# MCU.net
KiCad netlist of a schematic drawn in Altium Designer
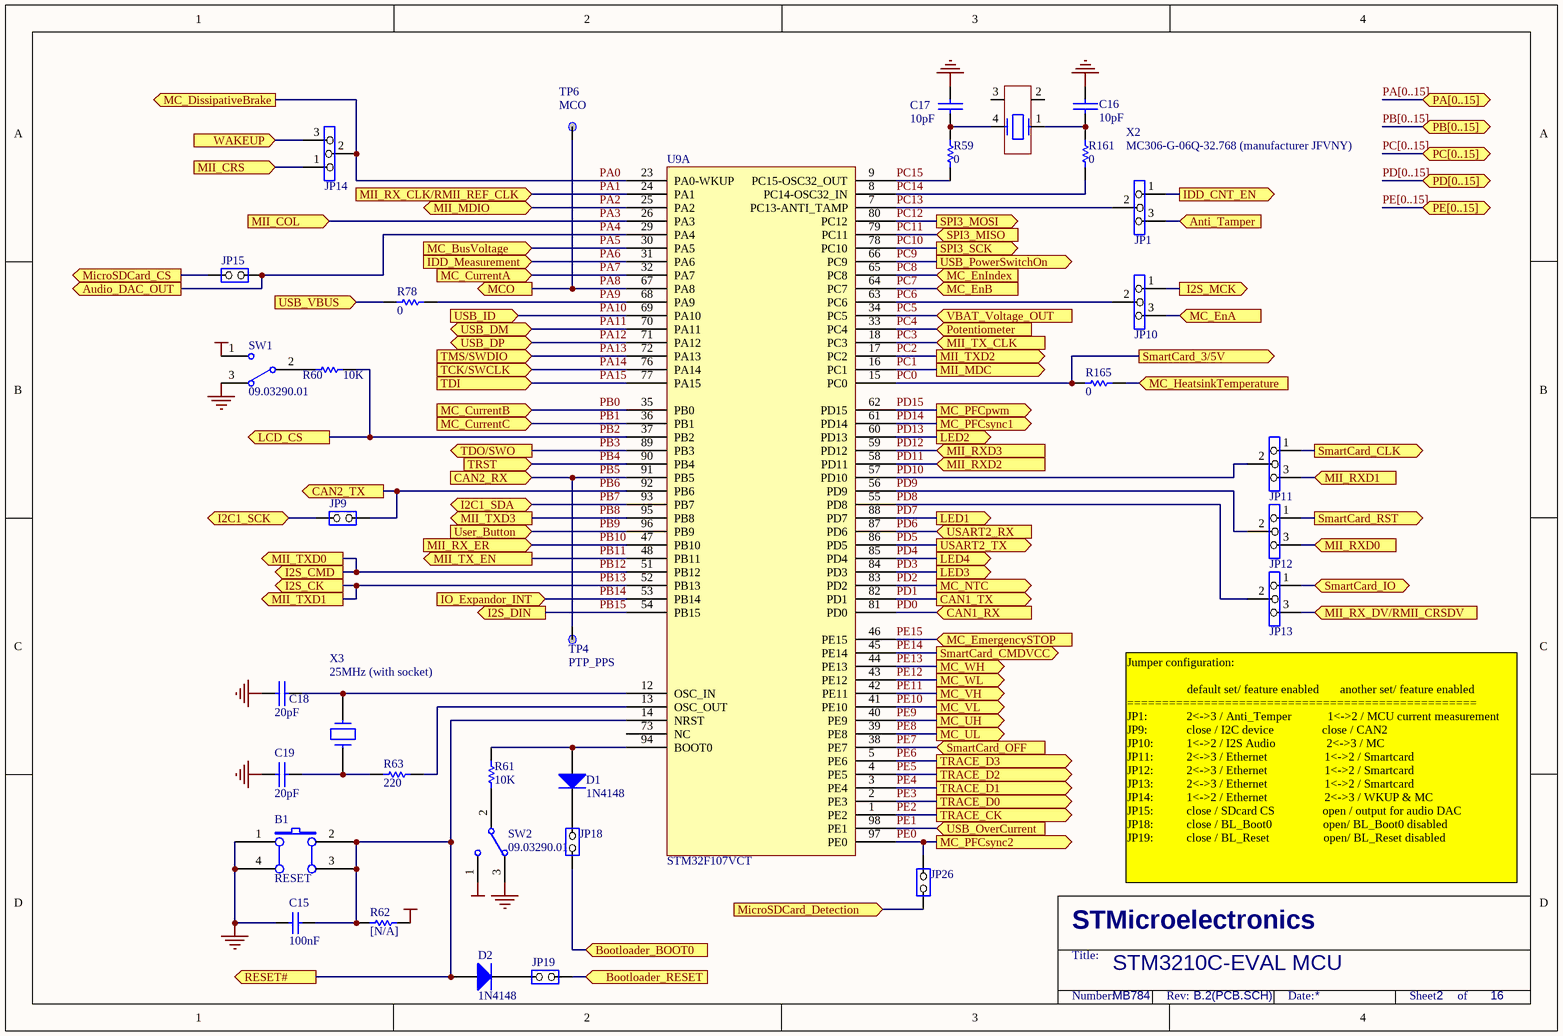
[diagram p0: MCU.SchDoc]

(export (version "E")
  (design (tool "Eeschema 10.0.6"))
  (components
    (comp (ref "B1")
      (value "RESET")
      (footprint "PB10")
      (description "SE PUSHBUTTON")
      (libsource (lib "Documents") (part "SW PUSHBUTTON"))
    )
    (comp (ref "C15")
      (value "100nF")
      (footprint "0603C")
      (description "Capacitor")
      (fields (field (name "PUBLISHER") "Altium Limited"))
      (libsource (lib "Miscellaneous Devices") (part "CAP"))
    )
    (comp (ref "C16")
      (value "10pF")
      (footprint "0603C")
      (description "Capacitor")
      (libsource (lib "") (part "CAP_1"))
    )
    (comp (ref "C17")
      (value "10pF")
      (footprint "0603C")
      (description "Capacitor")
      (libsource (lib "") (part "CAP_1"))
    )
    (comp (ref "C18")
      (value "20pF")
      (footprint "0603C")
      (description "Capacitor")
      (libsource (lib "*") (part "CAP"))
    )
    (comp (ref "C19")
      (value "20pF")
      (footprint "0603C")
      (description "Capacitor")
      (libsource (lib "*") (part "CAP"))
    )
    (comp (ref "D1")
      (value "1N4148")
      (footprint "1504D")
      (description "Default Diode")
      (fields (field (name "PUBLISHER") "Altium Limited"))
      (libsource (lib "Miscellaneous Devices") (part "Diode"))
    )
    (comp (ref "D2")
      (value "1N4148")
      (footprint "1504D")
      (description "Default Diode")
      (fields (field (name "PUBLISHER") "Altium Limited"))
      (libsource (lib "Miscellaneous Devices") (part "Diode"))
    )
    (comp (ref "JP1") (value "~") (footprint "SIP3") (libsource (lib "STR910_SCHLIB") (part "Jumper3")))
    (comp (ref "JP9") (value "~") (footprint "SIP2") (libsource (lib "*") (part "JP2")))
    (comp (ref "JP10") (value "~") (footprint "SIP3") (libsource (lib "STR910_SCHLIB") (part "Jumper3")))
    (comp (ref "JP11") (value "~") (footprint "SIP3") (libsource (lib "STR910_SCHLIB") (part "Jumper3")))
    (comp (ref "JP12") (value "~") (footprint "SIP3") (libsource (lib "STR910_SCHLIB") (part "Jumper3")))
    (comp (ref "JP13") (value "~") (footprint "SIP3") (libsource (lib "STR910_SCHLIB") (part "Jumper3")))
    (comp (ref "JP14") (value "~") (footprint "SIP3") (libsource (lib "STR910_SCHLIB") (part "Jumper3")))
    (comp (ref "JP15") (value "~") (footprint "SIP2") (libsource (lib "*") (part "JP2")))
    (comp (ref "JP18") (value "~") (footprint "SIP2") (libsource (lib "*") (part "JP2")))
    (comp (ref "JP19") (value "~") (footprint "SIP2") (libsource (lib "*") (part "JP2")))
    (comp (ref "JP26") (value "~") (footprint "SIP2") (libsource (lib "*") (part "JP2")))
    (comp (ref "R59")
      (value "0")
      (footprint "0603R")
      (description "Resistor")
      (fields (field (name "PUBLISHER") "Altium Limited"))
      (libsource (lib "Miscellaneous Devices") (part "Res1"))
    )
    (comp (ref "R60")
      (value "10K")
      (footprint "0603R")
      (description "Resistor")
      (fields (field (name "PUBLISHER") "Altium Limited"))
      (libsource (lib "Miscellaneous Devices") (part "res1"))
    )
    (comp (ref "R61")
      (value "10K")
      (footprint "0603R")
      (description "Resistor")
      (fields (field (name "PUBLISHER") "Altium Limited"))
      (libsource (lib "Miscellaneous Devices") (part "res1"))
    )
    (comp (ref "R62")
      (value "[N/A]")
      (footprint "0603R")
      (description "Resistor")
      (fields (field (name "PUBLISHER") "Altium Limited"))
      (libsource (lib "Miscellaneous Devices") (part "res1"))
    )
    (comp (ref "R63")
      (value "220")
      (footprint "0603R")
      (description "Resistor")
      (fields (field (name "PUBLISHER") "Altium Limited"))
      (libsource (lib "Miscellaneous Devices") (part "Res1"))
    )
    (comp (ref "R78")
      (value "0")
      (footprint "0603R")
      (description "Resistor")
      (fields (field (name "PUBLISHER") "Altium Limited"))
      (libsource (lib "Miscellaneous Devices") (part "Res1"))
    )
    (comp (ref "R161")
      (value "0")
      (footprint "0603R")
      (description "Resistor")
      (fields (field (name "PUBLISHER") "Altium Limited"))
      (libsource (lib "Miscellaneous Devices") (part "Res1"))
    )
    (comp (ref "R165")
      (value "0")
      (footprint "0603R")
      (description "Resistor")
      (fields (field (name "PUBLISHER") "Altium Limited"))
      (libsource (lib "Miscellaneous Devices") (part "Res1"))
    )
    (comp (ref "SW1")
      (value "09.03290.01")
      (footprint "SIP3")
      (description "SPDT Subminiature Toggle Switch, Right Angle Mounting, Vertical Actuation")
      (fields (field (name "PUBLISHER") "Altium Limited"))
      (libsource (lib "Miscellaneous Devices") (part "SW-SPDT"))
    )
    (comp (ref "SW2")
      (value "09.03290.01")
      (footprint "SIP3")
      (description "SPDT Subminiature Toggle Switch, Right Angle Mounting, Vertical Actuation")
      (fields (field (name "PUBLISHER") "Altium Limited"))
      (libsource (lib "Miscellaneous Devices") (part "SW-SPDT"))
    )
    (comp (ref "TP4") (value "PTP_PPS") (footprint "TP") (libsource (lib "*") (part "TP")))
    (comp (ref "TP6") (value "MCO") (footprint "TP") (libsource (lib "*") (part "TP")))
    (comp (ref "U9")
      (value "STM32F107VCT")
      (footprint "TQ100_TOOL")
      (libsource (lib "MB784") (part "BARRACUDA_256K"))
    )
    (comp (ref "X2")
      (value "MC306-G-06Q-32.768 (manufacturer JFVNY)")
      (footprint "SM8")
      (libsource (lib "*") (part "MC306"))
    )
    (comp (ref "X3")
      (value "25MHz (with socket)")
      (footprint "XTAL_socket")
      (description "Crystal")
      (libsource (lib "*") (part "CRYSTAL"))
    )
  )
  (nets
    (net (code "1") (name "+3V3") (class "Default")
      (node (ref "R62") (pin "2") (pinfunction "2_2") (pintype "passive"))
      (node (ref "SW1") (pin "1") (pintype "passive"))
      (node (ref "SW2") (pin "1") (pintype "passive"))
    )
    (net (code "2") (name "/Anti_Tamper") (class "Default") (node (ref "JP1") (pin "3") (pintype "passive")))
    (net (code "3") (name "/Bootloader_BOOT0") (class "Default")
      (node (ref "JP18") (pin "2") (pinfunction "NO_2") (pintype "passive"))
    )
    (net (code "4") (name "/Bootloader_RESET") (class "Default")
      (node (ref "JP19") (pin "2") (pinfunction "NO_2") (pintype "passive"))
    )
    (net (code "5") (name "/I2C1_SCK") (class "Default")
      (node (ref "JP9") (pin "2") (pinfunction "NO_2") (pintype "passive"))
    )
    (net (code "6") (name "/I2S_MCK") (class "Default") (node (ref "JP10") (pin "1") (pintype "passive")))
    (net (code "7") (name "/IDD_CNT_EN") (class "Default") (node (ref "JP1") (pin "1") (pintype "passive")))
    (net (code "8") (name "/MC_EnA") (class "Default") (node (ref "JP10") (pin "3") (pintype "passive")))
    (net (code "9") (name "/MC_HeatsinkTemperature") (class "Default")
      (node (ref "R165") (pin "2") (pinfunction "2_2") (pintype "passive"))
    )
    (net (code "10") (name "/MII_CRS") (class "Default") (node (ref "JP14") (pin "1") (pintype "passive")))
    (net (code "11") (name "/MII_RXD0") (class "Default") (node (ref "JP12") (pin "3") (pintype "passive")))
    (net (code "12") (name "/MII_RXD1") (class "Default") (node (ref "JP11") (pin "3") (pintype "passive")))
    (net (code "13") (name "/MII_RX_DV{slash}RMII_CRSDV") (class "Default")
      (node (ref "JP13") (pin "3") (pintype "passive"))
    )
    (net (code "14") (name "/MicroSDCard_CS") (class "Default")
      (node (ref "JP15") (pin "2") (pinfunction "NO_2") (pintype "passive"))
    )
    (net (code "15") (name "/MicroSDCard_Detection") (class "Default")
      (node (ref "JP26") (pin "1") (pinfunction "COMMON_1") (pintype "passive"))
    )
    (net (code "16") (name "/PA0") (class "Default")
      (node (ref "JP14") (pin "2") (pintype "passive"))
      (node (ref "U9") (pin "23") (pinfunction "PA0-WKUP_23") (pintype "passive"))
    )
    (net (code "17") (name "/PA1") (class "Default")
      (node (ref "U9") (pin "24") (pinfunction "PA1_24") (pintype "passive"))
    )
    (net (code "18") (name "/PA2") (class "Default")
      (node (ref "U9") (pin "25") (pinfunction "PA2_25") (pintype "passive"))
    )
    (net (code "19") (name "/PA3") (class "Default")
      (node (ref "U9") (pin "26") (pinfunction "PA3_26") (pintype "passive"))
    )
    (net (code "20") (name "/PA4") (class "Default")
      (node (ref "JP15") (pin "1") (pinfunction "COMMON_1") (pintype "passive"))
      (node (ref "U9") (pin "29") (pinfunction "PA4_29") (pintype "passive"))
    )
    (net (code "21") (name "/PA5") (class "Default")
      (node (ref "U9") (pin "30") (pinfunction "PA5_30") (pintype "passive"))
    )
    (net (code "22") (name "/PA6") (class "Default")
      (node (ref "U9") (pin "31") (pinfunction "PA6_31") (pintype "passive"))
    )
    (net (code "23") (name "/PA7") (class "Default")
      (node (ref "U9") (pin "32") (pinfunction "PA7_32") (pintype "passive"))
    )
    (net (code "24") (name "/PA8") (class "Default")
      (node (ref "TP6") (pin "1") (pinfunction "1_1") (pintype "passive"))
      (node (ref "U9") (pin "67") (pinfunction "PA8_67") (pintype "passive"))
    )
    (net (code "25") (name "/PA9") (class "Default")
      (node (ref "R78") (pin "2") (pinfunction "2_2") (pintype "passive"))
      (node (ref "U9") (pin "68") (pinfunction "PA9_68") (pintype "passive"))
    )
    (net (code "26") (name "/PA10") (class "Default")
      (node (ref "U9") (pin "69") (pinfunction "PA10_69") (pintype "passive"))
    )
    (net (code "27") (name "/PA11") (class "Default")
      (node (ref "U9") (pin "70") (pinfunction "PA11_70") (pintype "passive"))
    )
    (net (code "28") (name "/PA12") (class "Default")
      (node (ref "U9") (pin "71") (pinfunction "PA12_71") (pintype "passive"))
    )
    (net (code "29") (name "/PA13") (class "Default")
      (node (ref "U9") (pin "72") (pinfunction "PA13_72") (pintype "passive"))
    )
    (net (code "30") (name "/PA14") (class "Default")
      (node (ref "U9") (pin "76") (pinfunction "PA14_76") (pintype "passive"))
    )
    (net (code "31") (name "/PA15") (class "Default")
      (node (ref "U9") (pin "77") (pinfunction "PA15_77") (pintype "passive"))
    )
    (net (code "33") (name "/PB0") (class "Default")
      (node (ref "U9") (pin "35") (pinfunction "PB0_35") (pintype "passive"))
    )
    (net (code "34") (name "/PB1") (class "Default")
      (node (ref "U9") (pin "36") (pinfunction "PB1_36") (pintype "passive"))
    )
    (net (code "35") (name "/PB2") (class "Default")
      (node (ref "R60") (pin "1") (pinfunction "1_1") (pintype "passive"))
      (node (ref "U9") (pin "37") (pinfunction "PB2_37") (pintype "passive"))
    )
    (net (code "36") (name "/PB3") (class "Default")
      (node (ref "U9") (pin "89") (pinfunction "PB3_89") (pintype "passive"))
    )
    (net (code "37") (name "/PB4") (class "Default")
      (node (ref "U9") (pin "90") (pinfunction "PB4_90") (pintype "passive"))
    )
    (net (code "38") (name "/PB5") (class "Default")
      (node (ref "TP4") (pin "1") (pinfunction "1_1") (pintype "passive"))
      (node (ref "U9") (pin "91") (pinfunction "PB5_91") (pintype "passive"))
    )
    (net (code "39") (name "/PB6") (class "Default")
      (node (ref "JP9") (pin "1") (pinfunction "COMMON_1") (pintype "passive"))
      (node (ref "U9") (pin "92") (pinfunction "PB6_92") (pintype "passive"))
    )
    (net (code "40") (name "/PB7") (class "Default")
      (node (ref "U9") (pin "93") (pinfunction "PB7_93") (pintype "passive"))
    )
    (net (code "41") (name "/PB8") (class "Default")
      (node (ref "U9") (pin "95") (pinfunction "PB8_95") (pintype "passive"))
    )
    (net (code "42") (name "/PB9") (class "Default")
      (node (ref "U9") (pin "96") (pinfunction "PB9_96") (pintype "passive"))
    )
    (net (code "43") (name "/PB10") (class "Default")
      (node (ref "U9") (pin "47") (pinfunction "PB10_47") (pintype "passive"))
    )
    (net (code "44") (name "/PB11") (class "Default")
      (node (ref "U9") (pin "48") (pinfunction "PB11_48") (pintype "passive"))
    )
    (net (code "45") (name "/PB12") (class "Default")
      (node (ref "U9") (pin "51") (pinfunction "PB12_51") (pintype "passive"))
    )
    (net (code "46") (name "/PB13") (class "Default")
      (node (ref "U9") (pin "52") (pinfunction "PB13_52") (pintype "passive"))
    )
    (net (code "47") (name "/PB14") (class "Default")
      (node (ref "U9") (pin "53") (pinfunction "PB14_53") (pintype "passive"))
    )
    (net (code "48") (name "/PB15") (class "Default")
      (node (ref "U9") (pin "54") (pinfunction "PB15_54") (pintype "passive"))
    )
    (net (code "50") (name "/PC0") (class "Default")
      (node (ref "R165") (pin "1") (pinfunction "1_1") (pintype "passive"))
      (node (ref "U9") (pin "15") (pinfunction "PC0_15") (pintype "passive"))
    )
    (net (code "51") (name "/PC1") (class "Default")
      (node (ref "U9") (pin "16") (pinfunction "PC1_16") (pintype "passive"))
    )
    (net (code "52") (name "/PC2") (class "Default")
      (node (ref "U9") (pin "17") (pinfunction "PC2_17") (pintype "passive"))
    )
    (net (code "53") (name "/PC3") (class "Default")
      (node (ref "U9") (pin "18") (pinfunction "PC3_18") (pintype "passive"))
    )
    (net (code "54") (name "/PC4") (class "Default")
      (node (ref "U9") (pin "33") (pinfunction "PC4_33") (pintype "passive"))
    )
    (net (code "55") (name "/PC5") (class "Default")
      (node (ref "U9") (pin "34") (pinfunction "PC5_34") (pintype "passive"))
    )
    (net (code "56") (name "/PC6") (class "Default")
      (node (ref "JP10") (pin "2") (pintype "passive"))
      (node (ref "U9") (pin "63") (pinfunction "PC6_63") (pintype "passive"))
    )
    (net (code "57") (name "/PC7") (class "Default")
      (node (ref "U9") (pin "64") (pinfunction "PC7_64") (pintype "passive"))
    )
    (net (code "58") (name "/PC8") (class "Default")
      (node (ref "U9") (pin "65") (pinfunction "PC8_65") (pintype "passive"))
    )
    (net (code "59") (name "/PC9") (class "Default")
      (node (ref "U9") (pin "66") (pinfunction "PC9_66") (pintype "passive"))
    )
    (net (code "60") (name "/PC10") (class "Default")
      (node (ref "U9") (pin "78") (pinfunction "PC10_78") (pintype "passive"))
    )
    (net (code "61") (name "/PC11") (class "Default")
      (node (ref "U9") (pin "79") (pinfunction "PC11_79") (pintype "passive"))
    )
    (net (code "62") (name "/PC12") (class "Default")
      (node (ref "U9") (pin "80") (pinfunction "PC12_80") (pintype "passive"))
    )
    (net (code "63") (name "/PC13") (class "Default")
      (node (ref "JP1") (pin "2") (pintype "passive"))
      (node (ref "U9") (pin "7") (pinfunction "PC13-ANTI_TAMP_7") (pintype "passive"))
    )
    (net (code "64") (name "/PC14") (class "Default")
      (node (ref "R161") (pin "2") (pinfunction "2_2") (pintype "passive"))
      (node (ref "U9") (pin "8") (pinfunction "PC14-OSC32_IN_8") (pintype "passive"))
    )
    (net (code "65") (name "/PC15") (class "Default")
      (node (ref "R59") (pin "2") (pinfunction "2_2") (pintype "passive"))
      (node (ref "U9") (pin "9") (pinfunction "PC15-OSC32_OUT_9") (pintype "passive"))
    )
    (net (code "67") (name "/PD0") (class "Default")
      (node (ref "U9") (pin "81") (pinfunction "PD0_81") (pintype "passive"))
    )
    (net (code "68") (name "/PD1") (class "Default")
      (node (ref "U9") (pin "82") (pinfunction "PD1_82") (pintype "passive"))
    )
    (net (code "69") (name "/PD2") (class "Default")
      (node (ref "U9") (pin "83") (pinfunction "PD2_83") (pintype "passive"))
    )
    (net (code "70") (name "/PD3") (class "Default")
      (node (ref "U9") (pin "84") (pinfunction "PD3_84") (pintype "passive"))
    )
    (net (code "71") (name "/PD4") (class "Default")
      (node (ref "U9") (pin "85") (pinfunction "PD4_85") (pintype "passive"))
    )
    (net (code "72") (name "/PD5") (class "Default")
      (node (ref "U9") (pin "86") (pinfunction "PD5_86") (pintype "passive"))
    )
    (net (code "73") (name "/PD6") (class "Default")
      (node (ref "U9") (pin "87") (pinfunction "PD6_87") (pintype "passive"))
    )
    (net (code "74") (name "/PD7") (class "Default")
      (node (ref "U9") (pin "88") (pinfunction "PD7_88") (pintype "passive"))
    )
    (net (code "75") (name "/PD8") (class "Default")
      (node (ref "JP13") (pin "2") (pintype "passive"))
      (node (ref "U9") (pin "55") (pinfunction "PD8_55") (pintype "passive"))
    )
    (net (code "76") (name "/PD9") (class "Default")
      (node (ref "JP12") (pin "2") (pintype "passive"))
      (node (ref "U9") (pin "56") (pinfunction "PD9_56") (pintype "passive"))
    )
    (net (code "77") (name "/PD10") (class "Default")
      (node (ref "JP11") (pin "2") (pintype "passive"))
      (node (ref "U9") (pin "57") (pinfunction "PD10_57") (pintype "passive"))
    )
    (net (code "78") (name "/PD11") (class "Default")
      (node (ref "U9") (pin "58") (pinfunction "PD11_58") (pintype "passive"))
    )
    (net (code "79") (name "/PD12") (class "Default")
      (node (ref "U9") (pin "59") (pinfunction "PD12_59") (pintype "passive"))
    )
    (net (code "80") (name "/PD13") (class "Default")
      (node (ref "U9") (pin "60") (pinfunction "PD13_60") (pintype "passive"))
    )
    (net (code "81") (name "/PD14") (class "Default")
      (node (ref "U9") (pin "61") (pinfunction "PD14_61") (pintype "passive"))
    )
    (net (code "82") (name "/PD15") (class "Default")
      (node (ref "U9") (pin "62") (pinfunction "PD15_62") (pintype "passive"))
    )
    (net (code "84") (name "/PE0") (class "Default")
      (node (ref "JP26") (pin "2") (pinfunction "NO_2") (pintype "passive"))
      (node (ref "U9") (pin "97") (pinfunction "PE0_97") (pintype "passive"))
    )
    (net (code "85") (name "/PE1") (class "Default")
      (node (ref "U9") (pin "98") (pinfunction "PE1_98") (pintype "passive"))
    )
    (net (code "86") (name "/PE2") (class "Default")
      (node (ref "U9") (pin "1") (pinfunction "PE2_1") (pintype "passive"))
    )
    (net (code "87") (name "/PE3") (class "Default")
      (node (ref "U9") (pin "2") (pinfunction "PE3_2") (pintype "passive"))
    )
    (net (code "88") (name "/PE4") (class "Default")
      (node (ref "U9") (pin "3") (pinfunction "PE4_3") (pintype "passive"))
    )
    (net (code "89") (name "/PE5") (class "Default")
      (node (ref "U9") (pin "4") (pinfunction "PE5_4") (pintype "passive"))
    )
    (net (code "90") (name "/PE6") (class "Default")
      (node (ref "U9") (pin "5") (pinfunction "PE6_5") (pintype "passive"))
    )
    (net (code "91") (name "/PE7") (class "Default")
      (node (ref "U9") (pin "38") (pinfunction "PE7_38") (pintype "passive"))
    )
    (net (code "92") (name "/PE8") (class "Default")
      (node (ref "U9") (pin "39") (pinfunction "PE8_39") (pintype "passive"))
    )
    (net (code "93") (name "/PE9") (class "Default")
      (node (ref "U9") (pin "40") (pinfunction "PE9_40") (pintype "passive"))
    )
    (net (code "94") (name "/PE10") (class "Default")
      (node (ref "U9") (pin "41") (pinfunction "PE10_41") (pintype "passive"))
    )
    (net (code "95") (name "/PE11") (class "Default")
      (node (ref "U9") (pin "42") (pinfunction "PE11_42") (pintype "passive"))
    )
    (net (code "96") (name "/PE12") (class "Default")
      (node (ref "U9") (pin "43") (pinfunction "PE12_43") (pintype "passive"))
    )
    (net (code "97") (name "/PE13") (class "Default")
      (node (ref "U9") (pin "44") (pinfunction "PE13_44") (pintype "passive"))
    )
    (net (code "98") (name "/PE14") (class "Default")
      (node (ref "U9") (pin "45") (pinfunction "PE14_45") (pintype "passive"))
    )
    (net (code "99") (name "/PE15") (class "Default")
      (node (ref "U9") (pin "46") (pinfunction "PE15_46") (pintype "passive"))
    )
    (net (code "101") (name "/RESET#") (class "Default")
      (node (ref "B1") (pin "2") (pinfunction "B0_2") (pintype "passive"))
      (node (ref "B1") (pin "3") (pinfunction "B1_3") (pintype "passive"))
      (node (ref "C15") (pin "2") (pinfunction "2_2") (pintype "passive"))
      (node (ref "D2") (pin "1") (pinfunction "A_1") (pintype "passive"))
      (node (ref "R62") (pin "1") (pinfunction "1_1") (pintype "passive"))
      (node (ref "U9") (pin "14") (pinfunction "NRST_14") (pintype "passive"))
    )
    (net (code "102") (name "/SmartCard_CLK") (class "Default")
      (node (ref "JP11") (pin "1") (pintype "passive"))
    )
    (net (code "103") (name "/SmartCard_IO") (class "Default")
      (node (ref "JP13") (pin "1") (pintype "passive"))
    )
    (net (code "104") (name "/SmartCard_RST") (class "Default")
      (node (ref "JP12") (pin "1") (pintype "passive"))
    )
    (net (code "105") (name "/USB_VBUS") (class "Default")
      (node (ref "R78") (pin "1") (pinfunction "1_1") (pintype "passive"))
    )
    (net (code "106") (name "/WAKEUP") (class "Default") (node (ref "JP14") (pin "3") (pintype "passive")))
    (net (code "107") (name "GND") (class "Default")
      (node (ref "B1") (pin "1") (pinfunction "A0_1") (pintype "passive"))
      (node (ref "B1") (pin "4") (pinfunction "A1_4") (pintype "passive"))
      (node (ref "C15") (pin "1") (pinfunction "1_1") (pintype "passive"))
      (node (ref "C16") (pin "2") (pinfunction "2_2") (pintype "passive"))
      (node (ref "C17") (pin "2") (pinfunction "2_2") (pintype "passive"))
      (node (ref "C18") (pin "2") (pinfunction "2_2") (pintype "passive"))
      (node (ref "C19") (pin "2") (pinfunction "2_2") (pintype "passive"))
      (node (ref "SW1") (pin "3") (pintype "passive"))
      (node (ref "SW2") (pin "3") (pintype "passive"))
    )
    (net (code "108") (name "Net-(C16-Pad1)") (class "Default")
      (node (ref "C16") (pin "1") (pinfunction "1_1") (pintype "passive"))
      (node (ref "R161") (pin "1") (pinfunction "1_1") (pintype "passive"))
      (node (ref "X2") (pin "1") (pinfunction "1_1") (pintype "passive"))
    )
    (net (code "109") (name "Net-(C17-Pad1)") (class "Default")
      (node (ref "C17") (pin "1") (pinfunction "1_1") (pintype "passive"))
      (node (ref "R59") (pin "1") (pinfunction "1_1") (pintype "passive"))
      (node (ref "X2") (pin "4") (pinfunction "4_4") (pintype "passive"))
    )
    (net (code "110") (name "Net-(C19-Pad1)") (class "Default")
      (node (ref "C19") (pin "1") (pinfunction "1_1") (pintype "passive"))
      (node (ref "R63") (pin "2") (pinfunction "2_2") (pintype "passive"))
      (node (ref "X3") (pin "1") (pinfunction "1_1") (pintype "passive"))
    )
    (net (code "111") (name "Net-(D1-A)") (class "Default")
      (node (ref "D1") (pin "1") (pinfunction "A_1") (pintype "passive"))
      (node (ref "R61") (pin "1") (pinfunction "1_1") (pintype "passive"))
      (node (ref "U9") (pin "94") (pinfunction "BOOT0_94") (pintype "passive"))
    )
    (net (code "112") (name "Net-(D1-K)") (class "Default")
      (node (ref "D1") (pin "2") (pinfunction "K_2") (pintype "passive"))
      (node (ref "JP18") (pin "1") (pinfunction "COMMON_1") (pintype "passive"))
    )
    (net (code "113") (name "Net-(D2-K)") (class "Default")
      (node (ref "D2") (pin "2") (pinfunction "K_2") (pintype "passive"))
      (node (ref "JP19") (pin "1") (pinfunction "COMMON_1") (pintype "passive"))
    )
    (net (code "114") (name "Net-(R60-Pad2)") (class "Default")
      (node (ref "R60") (pin "2") (pinfunction "2_2") (pintype "passive"))
      (node (ref "SW1") (pin "2") (pintype "passive"))
    )
    (net (code "115") (name "Net-(R61-Pad2)") (class "Default")
      (node (ref "R61") (pin "2") (pinfunction "2_2") (pintype "passive"))
      (node (ref "SW2") (pin "2") (pintype "passive"))
    )
    (net (code "116") (name "Net-(U9A-OSC_IN)") (class "Default")
      (node (ref "C18") (pin "1") (pinfunction "1_1") (pintype "passive"))
      (node (ref "U9") (pin "12") (pinfunction "OSC_IN_12") (pintype "passive"))
      (node (ref "X3") (pin "2") (pinfunction "2_2") (pintype "passive"))
    )
    (net (code "117") (name "Net-(U9A-OSC_OUT)") (class "Default")
      (node (ref "R63") (pin "1") (pinfunction "1_1") (pintype "passive"))
      (node (ref "U9") (pin "13") (pinfunction "OSC_OUT_13") (pintype "passive"))
    )
    (net (code "118") (name "unconnected-(U9A-NC-Pad73)") (class "Default")
      (node (ref "U9") (pin "73") (pinfunction "NC_73") (pintype "passive"))
    )
    (net (code "119") (name "unconnected-(X2-Pad2)") (class "Default")
      (node (ref "X2") (pin "2") (pinfunction "2_2") (pintype "passive"))
    )
    (net (code "120") (name "unconnected-(X2-Pad3)") (class "Default")
      (node (ref "X2") (pin "3") (pinfunction "3_3") (pintype "passive"))
    )
  )
)
